# HeadTracker.net
KiCad netlist of a schematic drawn in Altium Designer
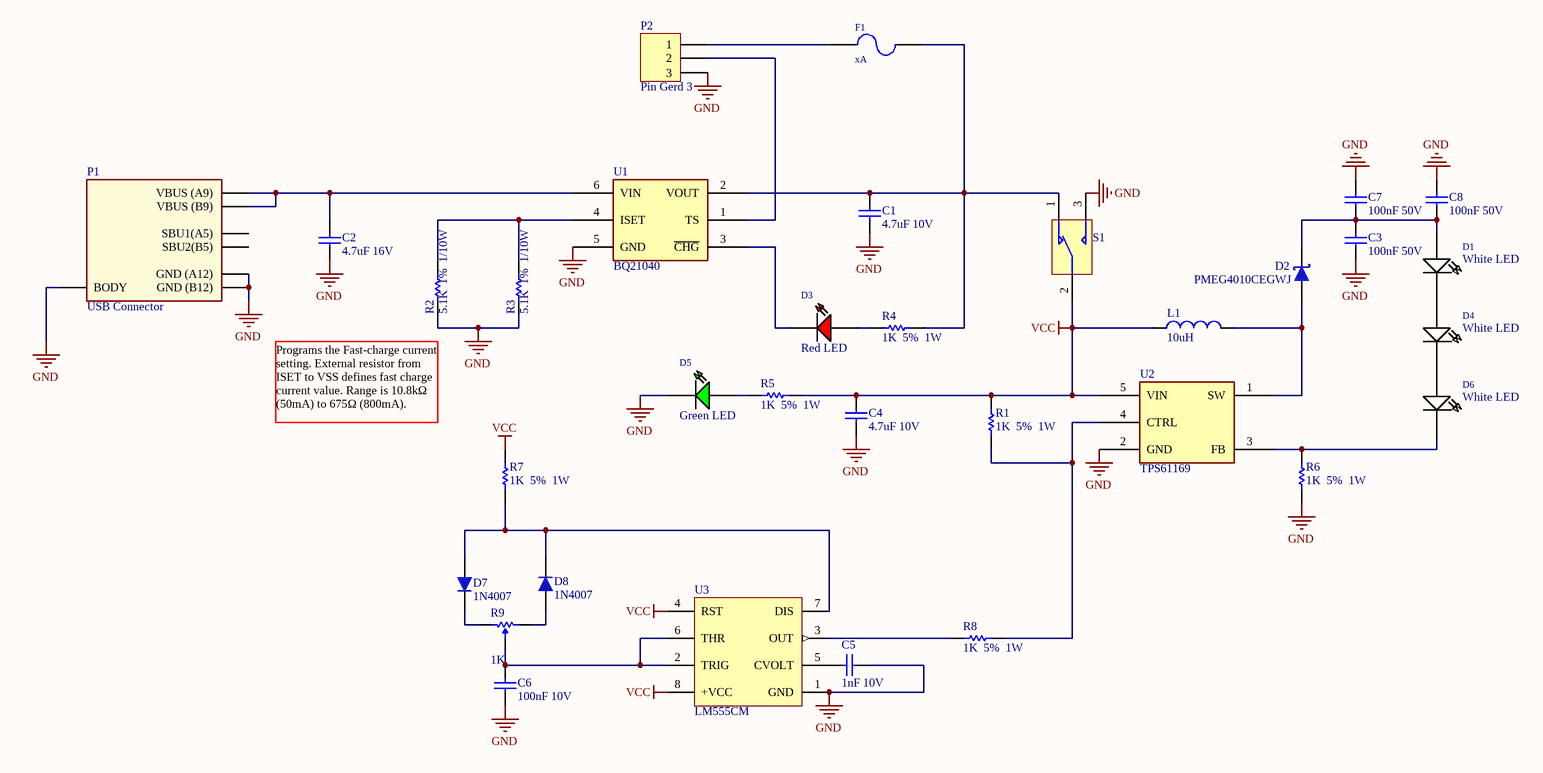
[diagram p0: HeadTracker.SchDoc]

(export (version "E")
  (design (tool "Eeschema 10.0.6"))
  (components
    (comp (ref "C1")
      (value "4.7uF 10V")
      (footprint "CAP0805")
      (description "Multilayer Ceramic Capacitors MLCC - SMD/SMT")
      (fields (field (name "TOLERANCE") "X7R 10%"))
      (libsource (lib "Passive Components") (part "Capacitor Ceramic - SMD"))
    )
    (comp (ref "C2")
      (value "4.7uF 16V")
      (footprint "CAP0805")
      (description "Multilayer Ceramic Capacitors MLCC - SMD/SMT")
      (fields (field (name "TOLERANCE") "X7R 10%"))
      (libsource (lib "Passive Components") (part "Capacitor Ceramic - SMD"))
    )
    (comp (ref "C3")
      (value "100nF 50V")
      (footprint "CAP0805")
      (description "Multilayer Ceramic Capacitors MLCC - SMD/SMT")
      (fields (field (name "TOLERANCE") "X7R 10%"))
      (libsource (lib "Passive Components") (part "Capacitor Ceramic - SMD"))
    )
    (comp (ref "C4")
      (value "4.7uF 10V")
      (footprint "CAP0805")
      (description "Multilayer Ceramic Capacitors MLCC - SMD/SMT")
      (fields (field (name "TOLERANCE") "X7R 10%"))
      (libsource (lib "Passive Components") (part "Capacitor Ceramic - SMD"))
    )
    (comp (ref "C5")
      (value "1nF 10V")
      (footprint "CAP0805")
      (description "Multilayer Ceramic Capacitors MLCC - SMD/SMT")
      (fields (field (name "TOLERANCE") "X7R 10%"))
      (libsource (lib "Passive Components") (part "Capacitor Ceramic - SMD"))
    )
    (comp (ref "C6")
      (value "100nF 10V")
      (footprint "CAP0805")
      (description "Multilayer Ceramic Capacitors MLCC - SMD/SMT")
      (fields (field (name "TOLERANCE") "X7R 10%"))
      (libsource (lib "Passive Components") (part "Capacitor Ceramic - SMD"))
    )
    (comp (ref "C7")
      (value "100nF 50V")
      (footprint "CAP0805")
      (description "Multilayer Ceramic Capacitors MLCC - SMD/SMT")
      (fields (field (name "TOLERANCE") "X7R 10%"))
      (libsource (lib "Passive Components") (part "Capacitor Ceramic - SMD"))
    )
    (comp (ref "C8")
      (value "100nF 50V")
      (footprint "CAP0805")
      (description "Multilayer Ceramic Capacitors MLCC - SMD/SMT")
      (fields (field (name "TOLERANCE") "X7R 10%"))
      (libsource (lib "Passive Components") (part "Capacitor Ceramic - SMD"))
    )
    (comp (ref "D1")
      (value "White LED")
      (footprint "LED_5mm - Right2")
      (description "Typical LED")
      (libsource (lib "Passive Components") (part "LED White"))
    )
    (comp (ref "D2")
      (value "PMEG4010CEGWJ")
      (footprint "DO-214-AC (SMA)")
      (description "Schottky Rectifiers")
      (fields (field (name "PARTNUMBER") "PMEG4010CEGWJ"))
      (libsource (lib "Active Components") (part "Diode Schottky"))
    )
    (comp (ref "D3")
      (value "Red LED")
      (footprint "LED_0805")
      (description "Typical LED")
      (libsource (lib "Passive Components") (part "LED Red"))
    )
    (comp (ref "D4")
      (value "White LED")
      (footprint "LED_5mm - Right2")
      (description "Typical LED")
      (libsource (lib "Passive Components") (part "LED White"))
    )
    (comp (ref "D5")
      (value "Green LED")
      (footprint "LED_0805")
      (description "Typical LED")
      (libsource (lib "Passive Components") (part "LED Green"))
    )
    (comp (ref "D6")
      (value "White LED")
      (footprint "LED_5mm - Right2")
      (description "Typical LED")
      (libsource (lib "Passive Components") (part "LED White"))
    )
    (comp (ref "D7")
      (value "1N4007")
      (footprint "DO-214-AA (SMB)")
      (description "Generic Diode")
      (fields (field (name "PARTNUMBER") "1N4007"))
      (libsource (lib "Active Components") (part "Diode"))
    )
    (comp (ref "D8")
      (value "1N4007")
      (footprint "DO-214-AA (SMB)")
      (description "Generic Diode")
      (fields (field (name "PARTNUMBER") "1N4007"))
      (libsource (lib "Active Components") (part "Diode"))
    )
    (comp (ref "F1")
      (value "xA")
      (footprint "Fuse_0805")
      (description "Fuses 5x20 with holdeer pins")
      (fields (field (name "TOLERANCE") "?%"))
      (libsource (lib "Passive Components") (part "Fuse"))
    )
    (comp (ref "L1")
      (value "10uH")
      (footprint "CDRH74")
      (description "Inductor")
      (fields (field (name "TOLERANCE") "?%"))
      (libsource (lib "Passive Components") (part "Inductor"))
    )
    (comp (ref "P1")
      (value "USB Connector")
      (footprint "USB TYPE-C 6P(073)")
      (description "USB Connector Type A")
      (fields (field (name "DESIGNER") "ABBAS BASEREH") (field (name "PUBLISHER") "ABBAS BASEREH"))
      (libsource (lib "Connectors") (part "USB C 6P"))
    )
    (comp (ref "P2")
      (value "Pin Gerd 3")
      (footprint "Pin Gerd S 3")
      (description "Stright")
      (libsource (lib "Connectors") (part "Pin Gerd 3"))
    )
    (comp (ref "R1")
      (value "1K  5%  1W")
      (footprint "RES0805")
      (description "Thick Film Resistor SMD")
      (fields (field (name "TOLERANCE") "5%") (field (name "POWER") "1W"))
      (libsource (lib "Passive Components") (part "Resistor Thick Film - SMD"))
    )
    (comp (ref "R2")
      (value "5.1K  1%  1/10W")
      (footprint "RES0805")
      (description "Thick Film Resistor SMD")
      (fields (field (name "TOLERANCE") "1%") (field (name "POWER") "1/10W"))
      (libsource (lib "Passive Components") (part "Resistor Thick Film - SMD"))
    )
    (comp (ref "R3")
      (value "5.1K  1%  1/10W")
      (footprint "RES0805")
      (description "Thick Film Resistor SMD")
      (fields (field (name "TOLERANCE") "1%") (field (name "POWER") "1/10W"))
      (libsource (lib "Passive Components") (part "Resistor Thick Film - SMD"))
    )
    (comp (ref "R4")
      (value "1K  5%  1W")
      (footprint "RES0805")
      (description "Thick Film Resistor SMD")
      (fields (field (name "TOLERANCE") "5%") (field (name "POWER") "1W"))
      (libsource (lib "Passive Components") (part "Resistor Thick Film - SMD"))
    )
    (comp (ref "R5")
      (value "1K  5%  1W")
      (footprint "RES0805")
      (description "Thick Film Resistor SMD")
      (fields (field (name "TOLERANCE") "5%") (field (name "POWER") "1W"))
      (libsource (lib "Passive Components") (part "Resistor Thick Film - SMD"))
    )
    (comp (ref "R6")
      (value "1K  5%  1W")
      (footprint "RES0805")
      (description "Thick Film Resistor SMD")
      (fields (field (name "TOLERANCE") "5%") (field (name "POWER") "1W"))
      (libsource (lib "Passive Components") (part "Resistor Thick Film - SMD"))
    )
    (comp (ref "R7")
      (value "1K  5%  1W")
      (footprint "RES0805")
      (description "Thick Film Resistor SMD")
      (fields (field (name "TOLERANCE") "5%") (field (name "POWER") "1W"))
      (libsource (lib "Passive Components") (part "Resistor Thick Film - SMD"))
    )
    (comp (ref "R8")
      (value "1K  5%  1W")
      (footprint "RES0805")
      (description "Thick Film Resistor SMD")
      (fields (field (name "TOLERANCE") "5%") (field (name "POWER") "1W"))
      (libsource (lib "Passive Components") (part "Resistor Thick Film - SMD"))
    )
    (comp (ref "R9")
      (value "1K")
      (footprint "POT 1")
      (description "Potentiometer")
      (fields (field (name "TOLERANCE") "?%"))
      (libsource (lib "Passive Components") (part "Potentiometer"))
    )
    (comp (ref "S1")
      (value "(Switch) SPDT_Subminiator")
      (footprint "SPDT Subminiator")
      (description "Subminiator SPDT Switch")
      (libsource (lib "Connectors") (part "(Switch) SPDT_Subminiator"))
    )
    (comp (ref "U1")
      (value "BQ21040")
      (footprint "SOT23-6")
      (description "bq21040 0.8-A, Single-Input, Single Cell Li-Ion and Li-Pol Battery Charger")
      (libsource (lib "Active Components") (part "BQ21040"))
    )
    (comp (ref "U2")
      (value "TPS61169")
      (footprint "SOT23-5")
      (description "TPS61169 38V High Current-Boost WLED Driver With PWM Control")
      (libsource (lib "Active Components") (part "TPS61169"))
    )
    (comp (ref "U3")
      (value "LM555CM")
      (footprint "SOIC 8-3.9mm")
      (description "Timer, 8-pin Narrow SOIC")
      (fields (field (name "PARTNUMBER") "LM555CM"))
      (libsource (lib "Active Components") (part "LM555CM"))
    )
  )
  (nets
    (net (code "1") (name "GND") (class "Default")
      (node (ref "C1") (pin "1") (pinfunction "1_1") (pintype "passive"))
      (node (ref "C2") (pin "1") (pinfunction "1_1") (pintype "passive"))
      (node (ref "C3") (pin "1") (pinfunction "1_1") (pintype "passive"))
      (node (ref "C4") (pin "1") (pinfunction "1_1") (pintype "passive"))
      (node (ref "C5") (pin "1") (pinfunction "1_1") (pintype "passive"))
      (node (ref "C6") (pin "1") (pinfunction "1_1") (pintype "passive"))
      (node (ref "C7") (pin "2") (pinfunction "2_2") (pintype "passive"))
      (node (ref "C8") (pin "2") (pinfunction "2_2") (pintype "passive"))
      (node (ref "D5") (pin "2") (pinfunction "K_2") (pintype "passive"))
      (node (ref "P1") (pin "0") (pinfunction "BODY_0") (pintype "power_in"))
      (node (ref "P1") (pin "A12") (pinfunction "GND_(A12)_A12") (pintype "power_in"))
      (node (ref "P1") (pin "B12") (pinfunction "GND_(B12)_B12") (pintype "power_in"))
      (node (ref "P2") (pin "3") (pinfunction "3_3") (pintype "passive"))
      (node (ref "R2") (pin "1") (pinfunction "1_1") (pintype "passive"))
      (node (ref "R3") (pin "1") (pinfunction "1_1") (pintype "passive"))
      (node (ref "R6") (pin "1") (pinfunction "1_1") (pintype "passive"))
      (node (ref "S1") (pin "3") (pinfunction "3_3") (pintype "passive"))
      (node (ref "U1") (pin "5") (pinfunction "GND_5") (pintype "passive"))
      (node (ref "U2") (pin "2") (pinfunction "GND_2") (pintype "passive"))
      (node (ref "U3") (pin "1") (pinfunction "GND_1") (pintype "power_in"))
    )
    (net (code "2") (name "Net-(D1-A)") (class "Default")
      (node (ref "C3") (pin "2") (pinfunction "2_2") (pintype "passive"))
      (node (ref "C7") (pin "1") (pinfunction "1_1") (pintype "passive"))
      (node (ref "C8") (pin "1") (pinfunction "1_1") (pintype "passive"))
      (node (ref "D1") (pin "1") (pinfunction "A_1") (pintype "passive"))
      (node (ref "D2") (pin "2") (pinfunction "K_2") (pintype "passive"))
    )
    (net (code "3") (name "Net-(D1-K)") (class "Default")
      (node (ref "D1") (pin "2") (pinfunction "K_2") (pintype "passive"))
      (node (ref "D4") (pin "1") (pinfunction "A_1") (pintype "passive"))
    )
    (net (code "4") (name "Net-(D2-A)") (class "Default")
      (node (ref "D2") (pin "1") (pinfunction "A_1") (pintype "passive"))
      (node (ref "L1") (pin "2") (pinfunction "2_2") (pintype "passive"))
      (node (ref "U2") (pin "1") (pinfunction "SW_1") (pintype "passive"))
    )
    (net (code "5") (name "Net-(D3-A)") (class "Default")
      (node (ref "D3") (pin "1") (pinfunction "A_1") (pintype "passive"))
      (node (ref "R4") (pin "1") (pinfunction "1_1") (pintype "passive"))
    )
    (net (code "6") (name "Net-(D3-K)") (class "Default")
      (node (ref "D3") (pin "2") (pinfunction "K_2") (pintype "passive"))
      (node (ref "U1") (pin "3") (pinfunction "~{CHG}_3") (pintype "passive"))
    )
    (net (code "7") (name "Net-(D4-K)") (class "Default")
      (node (ref "D4") (pin "2") (pinfunction "K_2") (pintype "passive"))
      (node (ref "D6") (pin "1") (pinfunction "A_1") (pintype "passive"))
    )
    (net (code "8") (name "Net-(D5-A)") (class "Default")
      (node (ref "D5") (pin "1") (pinfunction "A_1") (pintype "passive"))
      (node (ref "R5") (pin "1") (pinfunction "1_1") (pintype "passive"))
    )
    (net (code "9") (name "Net-(D6-K)") (class "Default")
      (node (ref "D6") (pin "2") (pinfunction "K_2") (pintype "passive"))
      (node (ref "R6") (pin "2") (pinfunction "2_2") (pintype "passive"))
      (node (ref "U2") (pin "3") (pinfunction "FB_3") (pintype "passive"))
    )
    (net (code "10") (name "Net-(D7-A)") (class "Default")
      (node (ref "D7") (pin "1") (pinfunction "A_1") (pintype "passive"))
      (node (ref "D8") (pin "2") (pinfunction "K_2") (pintype "passive"))
      (node (ref "R7") (pin "1") (pinfunction "1_1") (pintype "passive"))
      (node (ref "U3") (pin "7") (pinfunction "DIS_7") (pintype "open_collector"))
    )
    (net (code "11") (name "Net-(D7-K)") (class "Default")
      (node (ref "D7") (pin "2") (pinfunction "K_2") (pintype "passive"))
      (node (ref "R9") (pin "2") (pinfunction "2_2") (pintype "passive"))
    )
    (net (code "12") (name "Net-(D8-A)") (class "Default")
      (node (ref "D8") (pin "1") (pinfunction "A_1") (pintype "passive"))
      (node (ref "R9") (pin "1") (pinfunction "1_1") (pintype "passive"))
    )
    (net (code "13") (name "Net-(F1-Pad2)") (class "Default")
      (node (ref "F1") (pin "2") (pinfunction "2_2") (pintype "passive"))
      (node (ref "P2") (pin "1") (pinfunction "1_1") (pintype "passive"))
    )
    (net (code "14") (name "Net-(P1-VBUS_(A9))") (class "Default")
      (node (ref "C2") (pin "2") (pinfunction "2_2") (pintype "passive"))
      (node (ref "P1") (pin "A9") (pinfunction "VBUS_(A9)_A9") (pintype "power_in"))
      (node (ref "P1") (pin "B9") (pinfunction "VBUS_(B9)_B9") (pintype "power_in"))
      (node (ref "U1") (pin "6") (pinfunction "VIN_6") (pintype "passive"))
    )
    (net (code "15") (name "Net-(U1-ISET)") (class "Default")
      (node (ref "R2") (pin "2") (pinfunction "2_2") (pintype "passive"))
      (node (ref "R3") (pin "2") (pinfunction "2_2") (pintype "passive"))
      (node (ref "U1") (pin "4") (pinfunction "ISET_4") (pintype "passive"))
    )
    (net (code "16") (name "Net-(U1-TS)") (class "Default")
      (node (ref "P2") (pin "2") (pinfunction "2_2") (pintype "passive"))
      (node (ref "U1") (pin "1") (pinfunction "TS_1") (pintype "passive"))
    )
    (net (code "17") (name "Net-(U1-VOUT)") (class "Default")
      (node (ref "C1") (pin "2") (pinfunction "2_2") (pintype "passive"))
      (node (ref "F1") (pin "1") (pinfunction "1_1") (pintype "passive"))
      (node (ref "R4") (pin "2") (pinfunction "2_2") (pintype "passive"))
      (node (ref "S1") (pin "1") (pinfunction "1_1") (pintype "passive"))
      (node (ref "U1") (pin "2") (pinfunction "VOUT_2") (pintype "passive"))
    )
    (net (code "18") (name "Net-(U2-CTRL)") (class "Default")
      (node (ref "R1") (pin "1") (pinfunction "1_1") (pintype "passive"))
      (node (ref "R8") (pin "1") (pinfunction "1_1") (pintype "passive"))
      (node (ref "U2") (pin "4") (pinfunction "CTRL_4") (pintype "passive"))
    )
    (net (code "19") (name "Net-(U3-CVOLT)") (class "Default")
      (node (ref "C5") (pin "2") (pinfunction "2_2") (pintype "passive"))
      (node (ref "U3") (pin "5") (pinfunction "CVOLT_5") (pintype "passive"))
    )
    (net (code "20") (name "Net-(U3-OUT)") (class "Default")
      (node (ref "R8") (pin "2") (pinfunction "2_2") (pintype "passive"))
      (node (ref "U3") (pin "3") (pinfunction "OUT_3") (pintype "output"))
    )
    (net (code "21") (name "Net-(U3-THR)") (class "Default")
      (node (ref "C6") (pin "2") (pinfunction "2_2") (pintype "passive"))
      (node (ref "R9") (pin "3") (pinfunction "3_3") (pintype "passive"))
      (node (ref "U3") (pin "2") (pinfunction "TRIG_2") (pintype "passive"))
      (node (ref "U3") (pin "6") (pinfunction "THR_6") (pintype "passive"))
    )
    (net (code "22") (name "VCC") (class "Default")
      (node (ref "C4") (pin "2") (pinfunction "2_2") (pintype "passive"))
      (node (ref "L1") (pin "1") (pinfunction "1_1") (pintype "passive"))
      (node (ref "R1") (pin "2") (pinfunction "2_2") (pintype "passive"))
      (node (ref "R5") (pin "2") (pinfunction "2_2") (pintype "passive"))
      (node (ref "R7") (pin "2") (pinfunction "2_2") (pintype "passive"))
      (node (ref "S1") (pin "2") (pinfunction "2_2") (pintype "passive"))
      (node (ref "U2") (pin "5") (pinfunction "VIN_5") (pintype "passive"))
      (node (ref "U3") (pin "4") (pinfunction "RST_4") (pintype "passive"))
      (node (ref "U3") (pin "8") (pinfunction "+VCC_8") (pintype "power_in"))
    )
    (net (code "23") (name "unconnected-(P1-SBU1(A5)-PadA5)") (class "Default")
      (node (ref "P1") (pin "A5") (pinfunction "SBU1(A5)_A5") (pintype "power_in"))
    )
    (net (code "24") (name "unconnected-(P1-SBU2(B5)-PadB5)") (class "Default")
      (node (ref "P1") (pin "B5") (pinfunction "SBU2(B5)_B5") (pintype "power_in"))
    )
  )
)
